# pump-board-1_0.net
KiCad netlist of a schematic drawn in EAGLE
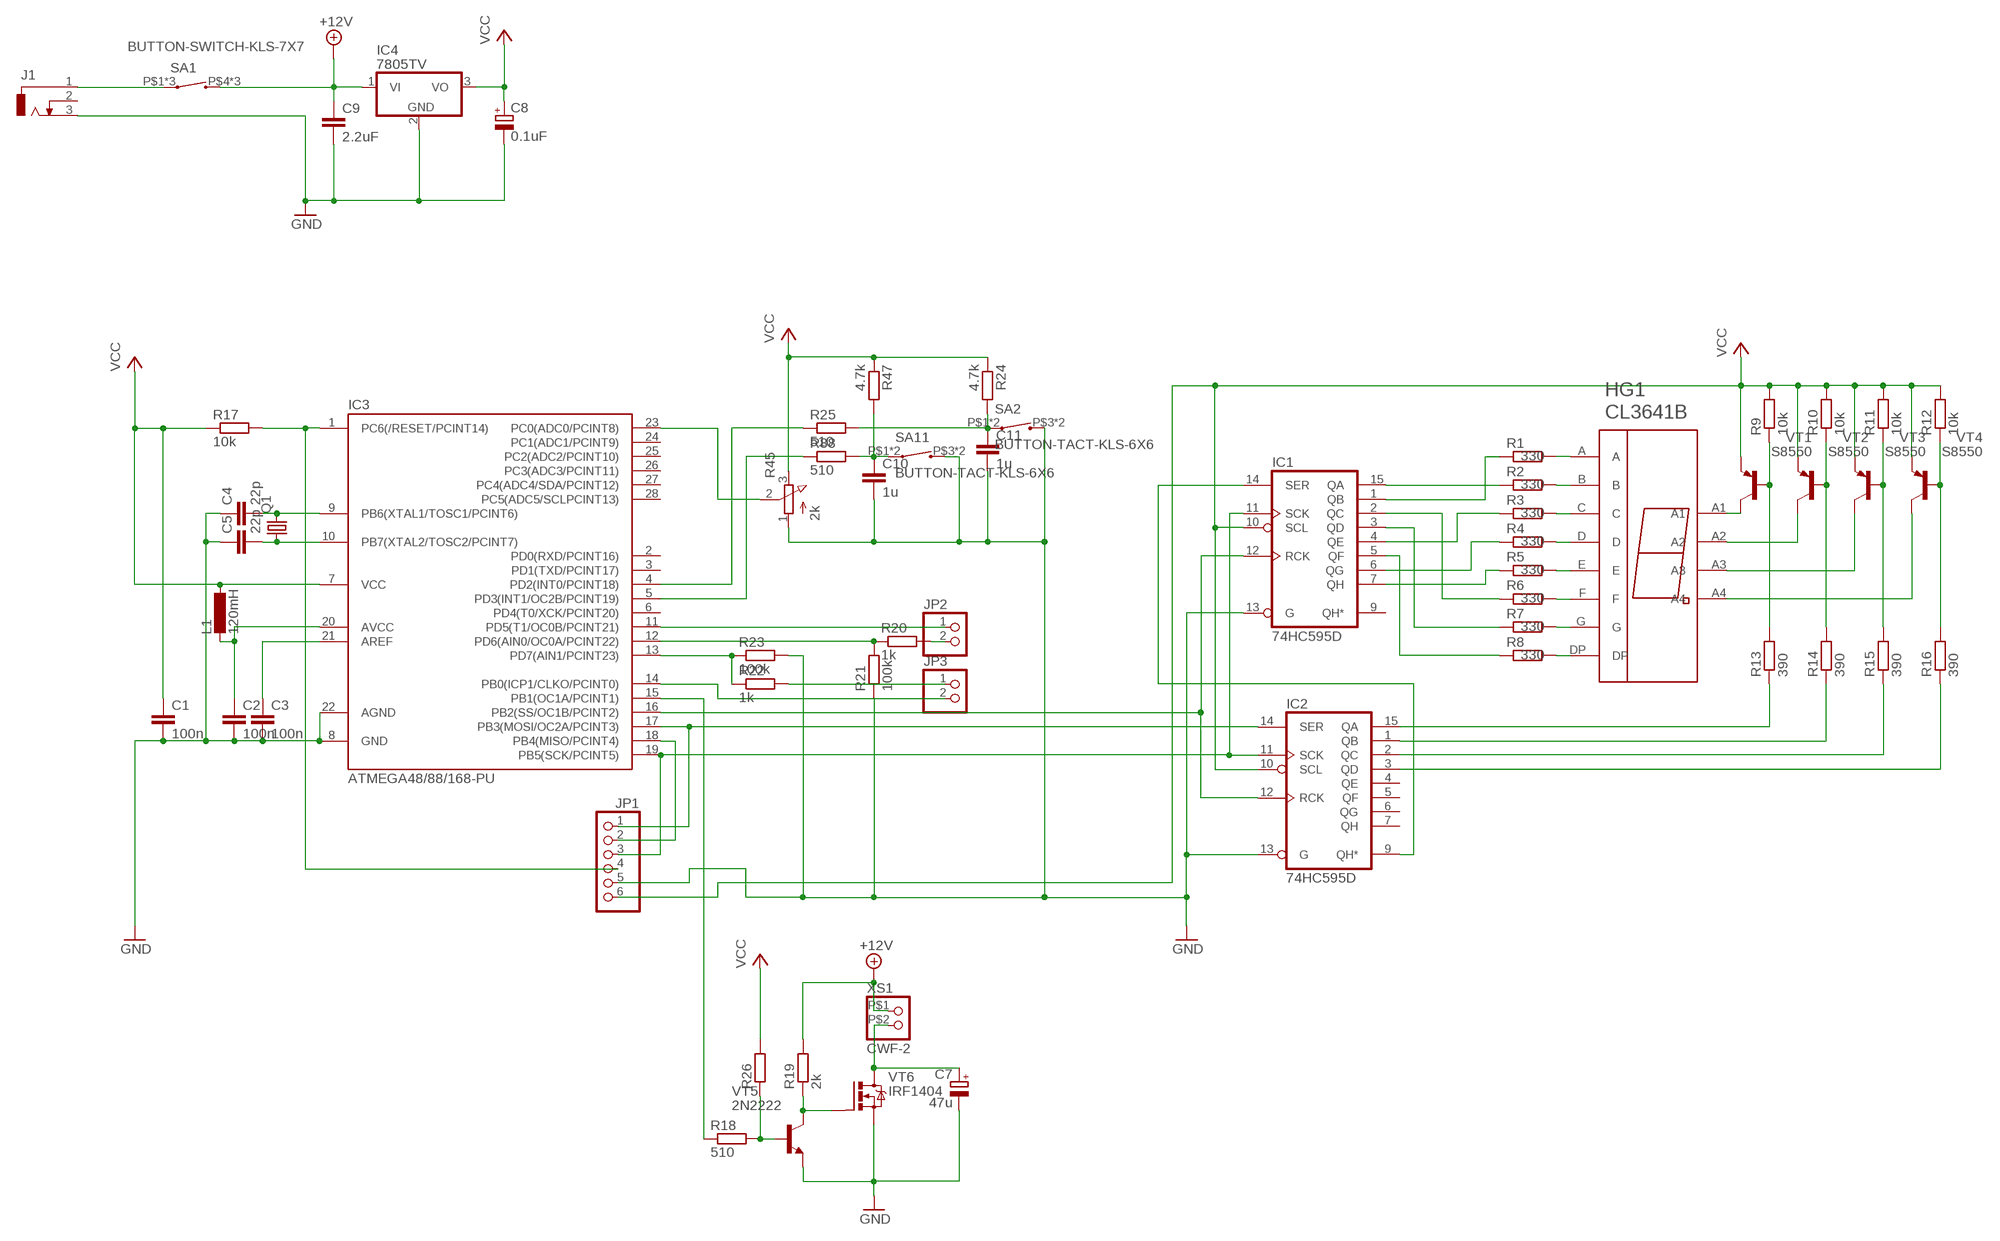
[diagram p0: schematic, sheet 1]

(export (version "E")
  (design (tool "Eeschema 10.0.6"))
  (components
    (comp (ref "C1")
      (value "100n")
      (footprint "eagle-import:C025-025X050")
      (libsource (lib "eagle-import") (part "rcl_334_C-EU025-025X050"))
    )
    (comp (ref "C2")
      (value "100n")
      (footprint "eagle-import:C1206")
      (libsource (lib "eagle-import") (part "rcl_334_C-EUC1206"))
    )
    (comp (ref "C3")
      (value "100n")
      (footprint "eagle-import:C1206")
      (libsource (lib "eagle-import") (part "rcl_334_C-EUC1206"))
    )
    (comp (ref "C4")
      (value "22p")
      (footprint "eagle-import:C1206")
      (libsource (lib "eagle-import") (part "rcl_334_C-EUC1206"))
    )
    (comp (ref "C5")
      (value "22p")
      (footprint "eagle-import:C1206")
      (libsource (lib "eagle-import") (part "rcl_334_C-EUC1206"))
    )
    (comp (ref "C7")
      (value "47u")
      (footprint "eagle-import:E2,5-5")
      (libsource (lib "eagle-import") (part "CPOL-EUE2.5-5"))
    )
    (comp (ref "C8")
      (value "0.1uF")
      (footprint "eagle-import:E2,5-5")
      (libsource (lib "eagle-import") (part "CPOL-EUE2.5-5"))
    )
    (comp (ref "C9")
      (value "2.2uF")
      (footprint "eagle-import:C025-025X050")
      (libsource (lib "eagle-import") (part "C-EU025-025X050"))
    )
    (comp (ref "C10")
      (value "1u")
      (footprint "eagle-import:C1206")
      (libsource (lib "eagle-import") (part "C-EUC1206"))
    )
    (comp (ref "C11")
      (value "1u")
      (footprint "eagle-import:C1206")
      (libsource (lib "eagle-import") (part "C-EUC1206"))
    )
    (comp (ref "HG1")
      (value "CL3641B")
      (footprint "eagle-import:CL3641B")
      (libsource (lib "eagle-import") (part "CL3641B"))
    )
    (comp (ref "IC1")
      (value "74HC595D")
      (footprint "eagle-import:SO16")
      (libsource (lib "eagle-import") (part "74595DHC"))
    )
    (comp (ref "IC2")
      (value "74HC595D")
      (footprint "eagle-import:SO16")
      (libsource (lib "eagle-import") (part "74595DHC"))
    )
    (comp (ref "IC3")
      (value "ATMEGA48/88/168-PU")
      (footprint "eagle-import:DIL28-3")
      (libsource (lib "eagle-import") (part "ATMEGA48/88/168-PU"))
    )
    (comp (ref "IC4")
      (value "7805TV")
      (footprint "eagle-import:TO220V")
      (libsource (lib "eagle-import") (part "78TV05"))
    )
    (comp (ref "J1")
      (value "DCJ0303")
      (footprint "eagle-import:DCJ0303")
      (libsource (lib "eagle-import") (part "DCJ0303"))
    )
    (comp (ref "JP1")
      (value "PINHD-1X6")
      (footprint "eagle-import:1X06")
      (libsource (lib "eagle-import") (part "PINHD-1X6"))
    )
    (comp (ref "JP2")
      (value "PINHD-1X2")
      (footprint "eagle-import:1X02")
      (libsource (lib "eagle-import") (part "PINHD-1X2"))
    )
    (comp (ref "JP3")
      (value "PINHD-1X2")
      (footprint "eagle-import:1X02")
      (libsource (lib "eagle-import") (part "PINHD-1X2"))
    )
    (comp (ref "L1")
      (value "120mH")
      (footprint "eagle-import:0207_10")
      (libsource (lib "eagle-import") (part "L-EU0207/10"))
    )
    (comp (ref "Q1")
      (value "CRYSTALHC49S")
      (footprint "eagle-import:HC49_S")
      (libsource (lib "eagle-import") (part "CRYSTALHC49S"))
    )
    (comp (ref "R1")
      (value "330")
      (footprint "eagle-import:R1206")
      (libsource (lib "eagle-import") (part "rcl_334_R-EU_R1206"))
    )
    (comp (ref "R2")
      (value "330")
      (footprint "eagle-import:R1206")
      (libsource (lib "eagle-import") (part "rcl_334_R-EU_R1206"))
    )
    (comp (ref "R3")
      (value "330")
      (footprint "eagle-import:R1206")
      (libsource (lib "eagle-import") (part "rcl_334_R-EU_R1206"))
    )
    (comp (ref "R4")
      (value "330")
      (footprint "eagle-import:R1206")
      (libsource (lib "eagle-import") (part "rcl_334_R-EU_R1206"))
    )
    (comp (ref "R5")
      (value "330")
      (footprint "eagle-import:R1206")
      (libsource (lib "eagle-import") (part "rcl_334_R-EU_R1206"))
    )
    (comp (ref "R6")
      (value "330")
      (footprint "eagle-import:R1206")
      (libsource (lib "eagle-import") (part "rcl_334_R-EU_R1206"))
    )
    (comp (ref "R7")
      (value "330")
      (footprint "eagle-import:R1206")
      (libsource (lib "eagle-import") (part "rcl_334_R-EU_R1206"))
    )
    (comp (ref "R8")
      (value "330")
      (footprint "eagle-import:R1206")
      (libsource (lib "eagle-import") (part "rcl_334_R-EU_R1206"))
    )
    (comp (ref "R9")
      (value "10k")
      (footprint "eagle-import:R1206")
      (libsource (lib "eagle-import") (part "rcl_334_R-EU_R1206"))
    )
    (comp (ref "R10")
      (value "10k")
      (footprint "eagle-import:R1206")
      (libsource (lib "eagle-import") (part "rcl_334_R-EU_R1206"))
    )
    (comp (ref "R11")
      (value "10k")
      (footprint "eagle-import:R1206")
      (libsource (lib "eagle-import") (part "rcl_334_R-EU_R1206"))
    )
    (comp (ref "R12")
      (value "10k")
      (footprint "eagle-import:R1206")
      (libsource (lib "eagle-import") (part "rcl_334_R-EU_R1206"))
    )
    (comp (ref "R13")
      (value "390")
      (footprint "eagle-import:R1206")
      (libsource (lib "eagle-import") (part "rcl_334_R-EU_R1206"))
    )
    (comp (ref "R14")
      (value "390")
      (footprint "eagle-import:R1206")
      (libsource (lib "eagle-import") (part "rcl_334_R-EU_R1206"))
    )
    (comp (ref "R15")
      (value "390")
      (footprint "eagle-import:R1206")
      (libsource (lib "eagle-import") (part "rcl_334_R-EU_R1206"))
    )
    (comp (ref "R16")
      (value "390")
      (footprint "eagle-import:R1206")
      (libsource (lib "eagle-import") (part "rcl_334_R-EU_R1206"))
    )
    (comp (ref "R17")
      (value "10k")
      (footprint "eagle-import:0207_10")
      (libsource (lib "eagle-import") (part "rcl_334_R-EU_0207/10"))
    )
    (comp (ref "R18")
      (value "510")
      (footprint "eagle-import:0207_10")
      (libsource (lib "eagle-import") (part "rcl_334_R-EU_0207/10"))
    )
    (comp (ref "R19")
      (value "2k")
      (footprint "eagle-import:R1206")
      (libsource (lib "eagle-import") (part "rcl_334_R-EU_R1206"))
    )
    (comp (ref "R20")
      (value "1k")
      (footprint "eagle-import:R1206")
      (libsource (lib "eagle-import") (part "rcl_334_R-EU_R1206"))
    )
    (comp (ref "R21")
      (value "100k")
      (footprint "eagle-import:R1206")
      (libsource (lib "eagle-import") (part "rcl_334_R-EU_R1206"))
    )
    (comp (ref "R22")
      (value "1k")
      (footprint "eagle-import:R1206")
      (libsource (lib "eagle-import") (part "rcl_334_R-EU_R1206"))
    )
    (comp (ref "R23")
      (value "100k")
      (footprint "eagle-import:R1206")
      (libsource (lib "eagle-import") (part "rcl_334_R-EU_R1206"))
    )
    (comp (ref "R24")
      (value "4.7k")
      (footprint "eagle-import:R1206")
      (libsource (lib "eagle-import") (part "R-EU_R1206"))
    )
    (comp (ref "R25")
      (value "510")
      (footprint "eagle-import:R1206")
      (libsource (lib "eagle-import") (part "R-EU_R1206"))
    )
    (comp (ref "R26")
      (value "R-EU_R1206")
      (footprint "eagle-import:R1206")
      (libsource (lib "eagle-import") (part "rcl_334_R-EU_R1206"))
    )
    (comp (ref "R45")
      (value "2k")
      (footprint "eagle-import:3RP_1610N")
      (libsource (lib "eagle-import") (part "3RP/1610N"))
    )
    (comp (ref "R47")
      (value "4.7k")
      (footprint "eagle-import:R1206")
      (libsource (lib "eagle-import") (part "R-EU_R1206"))
    )
    (comp (ref "R88")
      (value "510")
      (footprint "eagle-import:R1206")
      (libsource (lib "eagle-import") (part "R-EU_R1206"))
    )
    (comp (ref "SA1")
      (value "BUTTON-SWITCH-KLS-7X7")
      (footprint "eagle-import:KSL7-7X7")
      (libsource (lib "eagle-import") (part "BUTTON-SWITCH-KLS-7X7"))
    )
    (comp (ref "SA2")
      (value "BUTTON-TACT-KLS-6X6")
      (footprint "eagle-import:KLS7-6X6")
      (libsource (lib "eagle-import") (part "BUTTON-TACT-KLS-6X6"))
    )
    (comp (ref "SA11")
      (value "BUTTON-TACT-KLS-6X6")
      (footprint "eagle-import:KLS7-6X6")
      (libsource (lib "eagle-import") (part "BUTTON-TACT-KLS-6X6"))
    )
    (comp (ref "VT1")
      (value "S8550")
      (footprint "eagle-import:TO92")
      (libsource (lib "eagle-import") (part "S8550"))
    )
    (comp (ref "VT2")
      (value "S8550")
      (footprint "eagle-import:TO92")
      (libsource (lib "eagle-import") (part "S8550"))
    )
    (comp (ref "VT3")
      (value "S8550")
      (footprint "eagle-import:TO92")
      (libsource (lib "eagle-import") (part "S8550"))
    )
    (comp (ref "VT4")
      (value "S8550")
      (footprint "eagle-import:TO92")
      (libsource (lib "eagle-import") (part "S8550"))
    )
    (comp (ref "VT5")
      (value "2N2222")
      (footprint "eagle-import:TO92")
      (libsource (lib "eagle-import") (part "2N2222"))
    )
    (comp (ref "VT6")
      (value "IRF1404")
      (footprint "eagle-import:TO220-V")
      (libsource (lib "eagle-import") (part "IRF1404"))
    )
    (comp (ref "XS1")
      (value "CWF-2")
      (footprint "eagle-import:CWF-2")
      (libsource (lib "eagle-import") (part "CWF-2"))
    )
  )
  (nets
    (net (code "1") (name "+12V") (class "Default")
      (node (ref "C9") (pin "1") (pinfunction "1_1") (pintype "passive"))
      (node (ref "IC4") (pin "1") (pinfunction "VI_1") (pintype "input"))
      (node (ref "R19") (pin "2") (pinfunction "2_2") (pintype "passive"))
      (node (ref "SA1") (pin "P$4") (pinfunction "2_P$4") (pintype "passive"))
      (node (ref "SA1") (pin "P$5") (pinfunction "2_P$5") (pintype "passive"))
      (node (ref "SA1") (pin "P$6") (pinfunction "2_P$6") (pintype "passive"))
      (node (ref "XS1") (pin "P$1") (pinfunction "1_P$1") (pintype "passive"))
    )
    (net (code "2") (name "GND") (class "Default")
      (node (ref "C1") (pin "2") (pinfunction "2_2") (pintype "passive"))
      (node (ref "C10") (pin "2") (pinfunction "2_2") (pintype "passive"))
      (node (ref "C11") (pin "2") (pinfunction "2_2") (pintype "passive"))
      (node (ref "C2") (pin "2") (pinfunction "2_2") (pintype "passive"))
      (node (ref "C3") (pin "2") (pinfunction "2_2") (pintype "passive"))
      (node (ref "C4") (pin "1") (pinfunction "1_1") (pintype "passive"))
      (node (ref "C5") (pin "1") (pinfunction "1_1") (pintype "passive"))
      (node (ref "C7") (pin "-") (pinfunction "-_-") (pintype "passive"))
      (node (ref "C8") (pin "-") (pinfunction "-_-") (pintype "passive"))
      (node (ref "C9") (pin "2") (pinfunction "2_2") (pintype "passive"))
      (node (ref "IC1") (pin "13") (pinfunction "G_13") (pintype "input"))
      (node (ref "IC2") (pin "13") (pinfunction "G_13") (pintype "input"))
      (node (ref "IC3") (pin "22") (pinfunction "AGND_22") (pintype "power_in"))
      (node (ref "IC3") (pin "8") (pinfunction "GND_8") (pintype "power_in"))
      (node (ref "IC4") (pin "2") (pinfunction "GND_2") (pintype "passive"))
      (node (ref "J1") (pin "3") (pinfunction "3_3") (pintype "passive"))
      (node (ref "JP1") (pin "5") (pinfunction "5_5") (pintype "passive"))
      (node (ref "R21") (pin "1") (pinfunction "1_1") (pintype "passive"))
      (node (ref "R23") (pin "2") (pinfunction "2_2") (pintype "passive"))
      (node (ref "R45") (pin "1") (pinfunction "A_1") (pintype "passive"))
      (node (ref "SA11") (pin "P$3") (pinfunction "2_P$3") (pintype "passive"))
      (node (ref "SA11") (pin "P$4") (pinfunction "2_P$4") (pintype "passive"))
      (node (ref "SA2") (pin "P$3") (pinfunction "2_P$3") (pintype "passive"))
      (node (ref "SA2") (pin "P$4") (pinfunction "2_P$4") (pintype "passive"))
      (node (ref "VT5") (pin "3") (pinfunction "E_3") (pintype "passive"))
      (node (ref "VT6") (pin "S") (pinfunction "S_S") (pintype "passive"))
    )
    (net (code "3") (name "Net-(C10-Pad1)") (class "Default")
      (node (ref "C10") (pin "1") (pinfunction "1_1") (pintype "passive"))
      (node (ref "R47") (pin "2") (pinfunction "2_2") (pintype "passive"))
      (node (ref "R88") (pin "2") (pinfunction "2_2") (pintype "passive"))
      (node (ref "SA11") (pin "P$1") (pinfunction "1_P$1") (pintype "passive"))
      (node (ref "SA11") (pin "P$2") (pinfunction "1_P$2") (pintype "passive"))
    )
    (net (code "4") (name "Net-(C11-Pad1)") (class "Default")
      (node (ref "C11") (pin "1") (pinfunction "1_1") (pintype "passive"))
      (node (ref "R24") (pin "2") (pinfunction "2_2") (pintype "passive"))
      (node (ref "R25") (pin "2") (pinfunction "2_2") (pintype "passive"))
      (node (ref "SA2") (pin "P$1") (pinfunction "1_P$1") (pintype "passive"))
      (node (ref "SA2") (pin "P$2") (pinfunction "1_P$2") (pintype "passive"))
    )
    (net (code "5") (name "Net-(HG1-PadA)") (class "Default")
      (node (ref "HG1") (pin "A") (pinfunction "A_A") (pintype "output"))
      (node (ref "R1") (pin "2") (pinfunction "2_2") (pintype "passive"))
    )
    (net (code "6") (name "Net-(HG1-PadB)") (class "Default")
      (node (ref "HG1") (pin "B") (pinfunction "B_B") (pintype "output"))
      (node (ref "R2") (pin "2") (pinfunction "2_2") (pintype "passive"))
    )
    (net (code "7") (name "Net-(HG1-PadC)") (class "Default")
      (node (ref "HG1") (pin "C") (pinfunction "C_C") (pintype "output"))
      (node (ref "R3") (pin "2") (pinfunction "2_2") (pintype "passive"))
    )
    (net (code "8") (name "Net-(HG1-PadD)") (class "Default")
      (node (ref "HG1") (pin "D") (pinfunction "D_D") (pintype "output"))
      (node (ref "R4") (pin "2") (pinfunction "2_2") (pintype "passive"))
    )
    (net (code "9") (name "Net-(HG1-PadDP)") (class "Default")
      (node (ref "HG1") (pin "DP") (pinfunction "DP_DP") (pintype "output"))
      (node (ref "R8") (pin "2") (pinfunction "2_2") (pintype "passive"))
    )
    (net (code "10") (name "Net-(HG1-PadE)") (class "Default")
      (node (ref "HG1") (pin "E") (pinfunction "E_E") (pintype "output"))
      (node (ref "R5") (pin "2") (pinfunction "2_2") (pintype "passive"))
    )
    (net (code "11") (name "Net-(HG1-PadF)") (class "Default")
      (node (ref "HG1") (pin "F") (pinfunction "F_F") (pintype "output"))
      (node (ref "R6") (pin "2") (pinfunction "2_2") (pintype "passive"))
    )
    (net (code "12") (name "Net-(HG1-PadG)") (class "Default")
      (node (ref "HG1") (pin "G") (pinfunction "G_G") (pintype "output"))
      (node (ref "R7") (pin "2") (pinfunction "2_2") (pintype "passive"))
    )
    (net (code "13") (name "Net-(IC1A-QA)") (class "Default")
      (node (ref "IC1") (pin "15") (pinfunction "QA_15") (pintype "tri_state"))
      (node (ref "R2") (pin "1") (pinfunction "1_1") (pintype "passive"))
    )
    (net (code "14") (name "Net-(IC1A-QB)") (class "Default")
      (node (ref "IC1") (pin "1") (pinfunction "QB_1") (pintype "tri_state"))
      (node (ref "R1") (pin "1") (pinfunction "1_1") (pintype "passive"))
    )
    (net (code "15") (name "Net-(IC1A-QC)") (class "Default")
      (node (ref "IC1") (pin "2") (pinfunction "QC_2") (pintype "tri_state"))
      (node (ref "R6") (pin "1") (pinfunction "1_1") (pintype "passive"))
    )
    (net (code "16") (name "Net-(IC1A-QD)") (class "Default")
      (node (ref "IC1") (pin "3") (pinfunction "QD_3") (pintype "tri_state"))
      (node (ref "R7") (pin "1") (pinfunction "1_1") (pintype "passive"))
    )
    (net (code "17") (name "Net-(IC1A-QE)") (class "Default")
      (node (ref "IC1") (pin "4") (pinfunction "QE_4") (pintype "tri_state"))
      (node (ref "R3") (pin "1") (pinfunction "1_1") (pintype "passive"))
    )
    (net (code "18") (name "Net-(IC1A-QF)") (class "Default")
      (node (ref "IC1") (pin "5") (pinfunction "QF_5") (pintype "tri_state"))
      (node (ref "R8") (pin "1") (pinfunction "1_1") (pintype "passive"))
    )
    (net (code "19") (name "Net-(IC1A-QG)") (class "Default")
      (node (ref "IC1") (pin "6") (pinfunction "QG_6") (pintype "tri_state"))
      (node (ref "R4") (pin "1") (pinfunction "1_1") (pintype "passive"))
    )
    (net (code "20") (name "Net-(IC1A-QH)") (class "Default")
      (node (ref "IC1") (pin "7") (pinfunction "QH_7") (pintype "tri_state"))
      (node (ref "R5") (pin "1") (pinfunction "1_1") (pintype "passive"))
    )
    (net (code "21") (name "Net-(IC1A-RCK)") (class "Default")
      (node (ref "IC1") (pin "12") (pinfunction "RCK_12") (pintype "input"))
      (node (ref "IC2") (pin "12") (pinfunction "RCK_12") (pintype "input"))
      (node (ref "IC3") (pin "16") (pinfunction "PB2(SS/OC1B/PCINT2)_16") (pintype "bidirectional"))
    )
    (net (code "22") (name "Net-(IC1A-SCK)") (class "Default")
      (node (ref "IC1") (pin "11") (pinfunction "SCK_11") (pintype "input"))
      (node (ref "IC2") (pin "11") (pinfunction "SCK_11") (pintype "input"))
      (node (ref "IC3") (pin "19") (pinfunction "PB5(SCK/PCINT5)_19") (pintype "bidirectional"))
      (node (ref "JP1") (pin "3") (pinfunction "3_3") (pintype "passive"))
    )
    (net (code "23") (name "Net-(IC1A-SER)") (class "Default")
      (node (ref "IC1") (pin "14") (pinfunction "SER_14") (pintype "input"))
      (node (ref "IC2") (pin "9") (pinfunction "QH*_9") (pintype "tri_state"))
    )
    (net (code "24") (name "Net-(IC2A-QA)") (class "Default")
      (node (ref "IC2") (pin "15") (pinfunction "QA_15") (pintype "tri_state"))
      (node (ref "R13") (pin "1") (pinfunction "1_1") (pintype "passive"))
    )
    (net (code "25") (name "Net-(IC2A-QB)") (class "Default")
      (node (ref "IC2") (pin "1") (pinfunction "QB_1") (pintype "tri_state"))
      (node (ref "R14") (pin "1") (pinfunction "1_1") (pintype "passive"))
    )
    (net (code "26") (name "Net-(IC2A-QC)") (class "Default")
      (node (ref "IC2") (pin "2") (pinfunction "QC_2") (pintype "tri_state"))
      (node (ref "R15") (pin "1") (pinfunction "1_1") (pintype "passive"))
    )
    (net (code "27") (name "Net-(IC2A-QD)") (class "Default")
      (node (ref "IC2") (pin "3") (pinfunction "QD_3") (pintype "tri_state"))
      (node (ref "R16") (pin "1") (pinfunction "1_1") (pintype "passive"))
    )
    (net (code "28") (name "Net-(IC2A-SER)") (class "Default")
      (node (ref "IC2") (pin "14") (pinfunction "SER_14") (pintype "input"))
      (node (ref "IC3") (pin "17") (pinfunction "PB3(MOSI/OC2A/PCINT3)_17") (pintype "bidirectional"))
      (node (ref "JP1") (pin "1") (pinfunction "1_1") (pintype "passive"))
    )
    (net (code "29") (name "Net-(IC3-AREF)") (class "Default")
      (node (ref "C3") (pin "1") (pinfunction "1_1") (pintype "passive"))
      (node (ref "IC3") (pin "21") (pinfunction "AREF_21") (pintype "passive"))
    )
    (net (code "30") (name "Net-(IC3-AVCC)") (class "Default")
      (node (ref "C2") (pin "1") (pinfunction "1_1") (pintype "passive"))
      (node (ref "IC3") (pin "20") (pinfunction "AVCC_20") (pintype "passive"))
      (node (ref "L1") (pin "2") (pinfunction "2_2") (pintype "passive"))
    )
    (net (code "31") (name "Net-(IC3-PB0(ICP1{slash}CLKO{slash}PCINT0))") (class "Default")
      (node (ref "IC3") (pin "14") (pinfunction "PB0(ICP1/CLKO/PCINT0)_14") (pintype "bidirectional"))
      (node (ref "JP3") (pin "2") (pinfunction "2_2") (pintype "passive"))
    )
    (net (code "32") (name "Net-(IC3-PB1(OC1A{slash}PCINT1))") (class "Default")
      (node (ref "IC3") (pin "15") (pinfunction "PB1(OC1A/PCINT1)_15") (pintype "bidirectional"))
      (node (ref "R18") (pin "1") (pinfunction "1_1") (pintype "passive"))
    )
    (net (code "33") (name "Net-(IC3-PB4(MISO{slash}PCINT4))") (class "Default")
      (node (ref "IC3") (pin "18") (pinfunction "PB4(MISO/PCINT4)_18") (pintype "bidirectional"))
      (node (ref "JP1") (pin "2") (pinfunction "2_2") (pintype "passive"))
    )
    (net (code "34") (name "Net-(IC3-PB6(XTAL1{slash}TOSC1{slash}PCINT6))") (class "Default")
      (node (ref "C4") (pin "2") (pinfunction "2_2") (pintype "passive"))
      (node (ref "IC3") (pin "9") (pinfunction "PB6(XTAL1/TOSC1/PCINT6)_9") (pintype "bidirectional"))
      (node (ref "Q1") (pin "2") (pinfunction "2_2") (pintype "passive"))
    )
    (net (code "35") (name "Net-(IC3-PB7(XTAL2{slash}TOSC2{slash}PCINT7))") (class "Default")
      (node (ref "C5") (pin "2") (pinfunction "2_2") (pintype "passive"))
      (node (ref "IC3") (pin "10") (pinfunction "PB7(XTAL2/TOSC2/PCINT7)_10") (pintype "bidirectional"))
      (node (ref "Q1") (pin "1") (pinfunction "1_1") (pintype "passive"))
    )
    (net (code "36") (name "Net-(IC3-PC0(ADC0{slash}PCINT8))") (class "Default")
      (node (ref "IC3") (pin "23") (pinfunction "PC0(ADC0/PCINT8)_23") (pintype "bidirectional"))
      (node (ref "R45") (pin "2") (pinfunction "S_2") (pintype "passive"))
    )
    (net (code "37") (name "Net-(IC3-PC6({slash}RESET{slash}PCINT14))") (class "Default")
      (node (ref "IC3") (pin "1") (pinfunction "PC6(/RESET/PCINT14)_1") (pintype "bidirectional"))
      (node (ref "JP1") (pin "4") (pinfunction "4_4") (pintype "passive"))
      (node (ref "R17") (pin "2") (pinfunction "2_2") (pintype "passive"))
    )
    (net (code "38") (name "Net-(IC3-PD2(INT0{slash}PCINT18))") (class "Default")
      (node (ref "IC3") (pin "4") (pinfunction "PD2(INT0/PCINT18)_4") (pintype "bidirectional"))
      (node (ref "R25") (pin "1") (pinfunction "1_1") (pintype "passive"))
    )
    (net (code "39") (name "Net-(IC3-PD3(INT1{slash}OC2B{slash}PCINT19))") (class "Default")
      (node (ref "IC3") (pin "5") (pinfunction "PD3(INT1/OC2B/PCINT19)_5") (pintype "bidirectional"))
      (node (ref "R88") (pin "1") (pinfunction "1_1") (pintype "passive"))
    )
    (net (code "40") (name "Net-(IC3-PD5(T1{slash}OC0B{slash}PCINT21))") (class "Default")
      (node (ref "IC3") (pin "11") (pinfunction "PD5(T1/OC0B/PCINT21)_11") (pintype "bidirectional"))
      (node (ref "JP2") (pin "1") (pinfunction "1_1") (pintype "passive"))
    )
    (net (code "41") (name "Net-(IC3-PD6(AIN0{slash}OC0A{slash}PCINT22))") (class "Default")
      (node (ref "IC3") (pin "12") (pinfunction "PD6(AIN0/OC0A/PCINT22)_12") (pintype "bidirectional"))
      (node (ref "R20") (pin "1") (pinfunction "1_1") (pintype "passive"))
      (node (ref "R21") (pin "2") (pinfunction "2_2") (pintype "passive"))
    )
    (net (code "42") (name "Net-(IC3-PD7(AIN1{slash}PCINT23))") (class "Default")
      (node (ref "IC3") (pin "13") (pinfunction "PD7(AIN1/PCINT23)_13") (pintype "bidirectional"))
      (node (ref "R22") (pin "1") (pinfunction "1_1") (pintype "passive"))
      (node (ref "R23") (pin "1") (pinfunction "1_1") (pintype "passive"))
    )
    (net (code "43") (name "Net-(J1-Pad1)") (class "Default")
      (node (ref "J1") (pin "1") (pinfunction "1_1") (pintype "passive"))
      (node (ref "SA1") (pin "P$1") (pinfunction "1_P$1") (pintype "passive"))
      (node (ref "SA1") (pin "P$2") (pinfunction "1_P$2") (pintype "passive"))
      (node (ref "SA1") (pin "P$3") (pinfunction "1_P$3") (pintype "passive"))
    )
    (net (code "44") (name "Net-(JP2-Pad2)") (class "Default")
      (node (ref "JP2") (pin "2") (pinfunction "2_2") (pintype "passive"))
      (node (ref "R20") (pin "2") (pinfunction "2_2") (pintype "passive"))
    )
    (net (code "45") (name "Net-(JP3-Pad1)") (class "Default")
      (node (ref "JP3") (pin "1") (pinfunction "1_1") (pintype "passive"))
      (node (ref "R22") (pin "2") (pinfunction "2_2") (pintype "passive"))
    )
    (net (code "46") (name "Net-(VT1-B)") (class "Default")
      (node (ref "R13") (pin "2") (pinfunction "2_2") (pintype "passive"))
      (node (ref "R9") (pin "1") (pinfunction "1_1") (pintype "passive"))
      (node (ref "VT1") (pin "2") (pinfunction "B_2") (pintype "passive"))
    )
    (net (code "47") (name "Net-(VT1-C)") (class "Default")
      (node (ref "HG1") (pin "A1") (pinfunction "A1_A1") (pintype "input"))
      (node (ref "VT1") (pin "1") (pinfunction "C_1") (pintype "passive"))
    )
    (net (code "48") (name "Net-(VT2-B)") (class "Default")
      (node (ref "R10") (pin "1") (pinfunction "1_1") (pintype "passive"))
      (node (ref "R14") (pin "2") (pinfunction "2_2") (pintype "passive"))
      (node (ref "VT2") (pin "2") (pinfunction "B_2") (pintype "passive"))
    )
    (net (code "49") (name "Net-(VT2-C)") (class "Default")
      (node (ref "HG1") (pin "A2") (pinfunction "A2_A2") (pintype "input"))
      (node (ref "VT2") (pin "1") (pinfunction "C_1") (pintype "passive"))
    )
    (net (code "50") (name "Net-(VT3-B)") (class "Default")
      (node (ref "R11") (pin "1") (pinfunction "1_1") (pintype "passive"))
      (node (ref "R15") (pin "2") (pinfunction "2_2") (pintype "passive"))
      (node (ref "VT3") (pin "2") (pinfunction "B_2") (pintype "passive"))
    )
    (net (code "51") (name "Net-(VT3-C)") (class "Default")
      (node (ref "HG1") (pin "A3") (pinfunction "A3_A3") (pintype "input"))
      (node (ref "VT3") (pin "1") (pinfunction "C_1") (pintype "passive"))
    )
    (net (code "52") (name "Net-(VT4-B)") (class "Default")
      (node (ref "R12") (pin "1") (pinfunction "1_1") (pintype "passive"))
      (node (ref "R16") (pin "2") (pinfunction "2_2") (pintype "passive"))
      (node (ref "VT4") (pin "2") (pinfunction "B_2") (pintype "passive"))
    )
    (net (code "53") (name "Net-(VT4-C)") (class "Default")
      (node (ref "HG1") (pin "A4") (pinfunction "A4_A4") (pintype "input"))
      (node (ref "VT4") (pin "1") (pinfunction "C_1") (pintype "passive"))
    )
    (net (code "54") (name "Net-(VT5-B)") (class "Default")
      (node (ref "R18") (pin "2") (pinfunction "2_2") (pintype "passive"))
      (node (ref "R26") (pin "1") (pinfunction "1_1") (pintype "passive"))
      (node (ref "VT5") (pin "2") (pinfunction "B_2") (pintype "passive"))
    )
    (net (code "55") (name "Net-(VT5-C)") (class "Default")
      (node (ref "R19") (pin "1") (pinfunction "1_1") (pintype "passive"))
      (node (ref "VT5") (pin "1") (pinfunction "C_1") (pintype "passive"))
      (node (ref "VT6") (pin "G") (pinfunction "G_G") (pintype "passive"))
    )
    (net (code "56") (name "Net-(XS1-2)") (class "Default")
      (node (ref "C7") (pin "+") (pinfunction "+_+") (pintype "passive"))
      (node (ref "VT6") (pin "D") (pinfunction "D_D") (pintype "passive"))
      (node (ref "XS1") (pin "P$2") (pinfunction "2_P$2") (pintype "passive"))
    )
    (net (code "57") (name "VCC") (class "Default")
      (node (ref "C1") (pin "1") (pinfunction "1_1") (pintype "passive"))
      (node (ref "C8") (pin "+") (pinfunction "+_+") (pintype "passive"))
      (node (ref "IC1") (pin "10") (pinfunction "SCL_10") (pintype "input"))
      (node (ref "IC2") (pin "10") (pinfunction "SCL_10") (pintype "input"))
      (node (ref "IC3") (pin "7") (pinfunction "VCC_7") (pintype "power_in"))
      (node (ref "IC4") (pin "3") (pinfunction "VO_3") (pintype "passive"))
      (node (ref "JP1") (pin "6") (pinfunction "6_6") (pintype "passive"))
      (node (ref "L1") (pin "1") (pinfunction "1_1") (pintype "passive"))
      (node (ref "R10") (pin "2") (pinfunction "2_2") (pintype "passive"))
      (node (ref "R11") (pin "2") (pinfunction "2_2") (pintype "passive"))
      (node (ref "R12") (pin "2") (pinfunction "2_2") (pintype "passive"))
      (node (ref "R17") (pin "1") (pinfunction "1_1") (pintype "passive"))
      (node (ref "R24") (pin "1") (pinfunction "1_1") (pintype "passive"))
      (node (ref "R26") (pin "2") (pinfunction "2_2") (pintype "passive"))
      (node (ref "R45") (pin "3") (pinfunction "E_3") (pintype "passive"))
      (node (ref "R47") (pin "1") (pinfunction "1_1") (pintype "passive"))
      (node (ref "R9") (pin "2") (pinfunction "2_2") (pintype "passive"))
      (node (ref "VT1") (pin "3") (pinfunction "E_3") (pintype "passive"))
      (node (ref "VT2") (pin "3") (pinfunction "E_3") (pintype "passive"))
      (node (ref "VT3") (pin "3") (pinfunction "E_3") (pintype "passive"))
      (node (ref "VT4") (pin "3") (pinfunction "E_3") (pintype "passive"))
    )
    (net (code "58") (name "unconnected-(IC1A-QH*-Pad9)") (class "Default")
      (node (ref "IC1") (pin "9") (pinfunction "QH*_9") (pintype "tri_state"))
    )
    (net (code "59") (name "unconnected-(IC2A-QE-Pad4)") (class "Default")
      (node (ref "IC2") (pin "4") (pinfunction "QE_4") (pintype "tri_state"))
    )
    (net (code "60") (name "unconnected-(IC2A-QF-Pad5)") (class "Default")
      (node (ref "IC2") (pin "5") (pinfunction "QF_5") (pintype "tri_state"))
    )
    (net (code "61") (name "unconnected-(IC2A-QG-Pad6)") (class "Default")
      (node (ref "IC2") (pin "6") (pinfunction "QG_6") (pintype "tri_state"))
    )
    (net (code "62") (name "unconnected-(IC2A-QH-Pad7)") (class "Default")
      (node (ref "IC2") (pin "7") (pinfunction "QH_7") (pintype "tri_state"))
    )
    (net (code "63") (name "unconnected-(IC3-PC1(ADC1{slash}PCINT9)-Pad24)") (class "Default")
      (node (ref "IC3") (pin "24") (pinfunction "PC1(ADC1/PCINT9)_24") (pintype "bidirectional"))
    )
    (net (code "64") (name "unconnected-(IC3-PC2(ADC2{slash}PCINT10)-Pad25)") (class "Default")
      (node (ref "IC3") (pin "25") (pinfunction "PC2(ADC2/PCINT10)_25") (pintype "bidirectional"))
    )
    (net (code "65") (name "unconnected-(IC3-PC3(ADC3{slash}PCINT11)-Pad26)") (class "Default")
      (node (ref "IC3") (pin "26") (pinfunction "PC3(ADC3/PCINT11)_26") (pintype "bidirectional"))
    )
    (net (code "66") (name "unconnected-(IC3-PC4(ADC4{slash}SDA{slash}PCINT12)-Pad27)") (class "Default")
      (node (ref "IC3") (pin "27") (pinfunction "PC4(ADC4/SDA/PCINT12)_27") (pintype "bidirectional"))
    )
    (net (code "67") (name "unconnected-(IC3-PC5(ADC5{slash}SCLPCINT13)-Pad28)") (class "Default")
      (node (ref "IC3") (pin "28") (pinfunction "PC5(ADC5/SCLPCINT13)_28") (pintype "bidirectional"))
    )
    (net (code "68") (name "unconnected-(IC3-PD0(RXD{slash}PCINT16)-Pad2)") (class "Default")
      (node (ref "IC3") (pin "2") (pinfunction "PD0(RXD/PCINT16)_2") (pintype "bidirectional"))
    )
    (net (code "69") (name "unconnected-(IC3-PD1(TXD{slash}PCINT17)-Pad3)") (class "Default")
      (node (ref "IC3") (pin "3") (pinfunction "PD1(TXD/PCINT17)_3") (pintype "bidirectional"))
    )
    (net (code "70") (name "unconnected-(IC3-PD4(T0{slash}XCK{slash}PCINT20)-Pad6)") (class "Default")
      (node (ref "IC3") (pin "6") (pinfunction "PD4(T0/XCK/PCINT20)_6") (pintype "bidirectional"))
    )
    (net (code "71") (name "unconnected-(J1-Pad2)") (class "Default")
      (node (ref "J1") (pin "2") (pinfunction "2_2") (pintype "passive"))
    )
  )
)
